# Sensor_Subsystem_Gas_Monitoring.net
KiCad netlist of a schematic drawn in Altium Designer
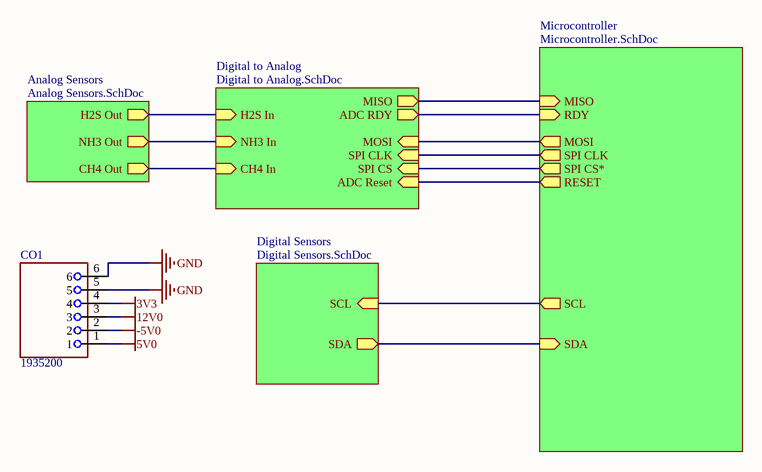
[diagram p0: Sensor Subsystem Gas Monitoring.SchDoc]

(export (version "E")
  (design (tool "Eeschema 10.0.6"))
  (components
    (comp (ref "CO1")
      (value "1935200")
      (footprint "PHOENIX_1935200")
      (fields (field (name "MF") "Littelfuse"))
      (libsource (lib "Main Connector") (part "1935200"))
    )
  )
  (nets
    (net (code "1") (name "-5V0") (class "Default")
      (node (ref "CO1") (pin "2") (pinfunction "2_2") (pintype "passive"))
    )
    (net (code "13") (name "3V3") (class "Default")
      (node (ref "CO1") (pin "4") (pinfunction "4_4") (pintype "passive"))
    )
    (net (code "14") (name "5V0") (class "Default")
      (node (ref "CO1") (pin "1") (pinfunction "1_1") (pintype "passive"))
    )
    (net (code "15") (name "12V0") (class "Default")
      (node (ref "CO1") (pin "3") (pinfunction "3_3") (pintype "passive"))
    )
    (net (code "16") (name "GND") (class "Default")
      (node (ref "CO1") (pin "5") (pinfunction "5_5") (pintype "passive"))
      (node (ref "CO1") (pin "6") (pinfunction "6_6") (pintype "passive"))
    )
  )
)
